# pin.net
KiCad netlist of a schematic drawn in EAGLE
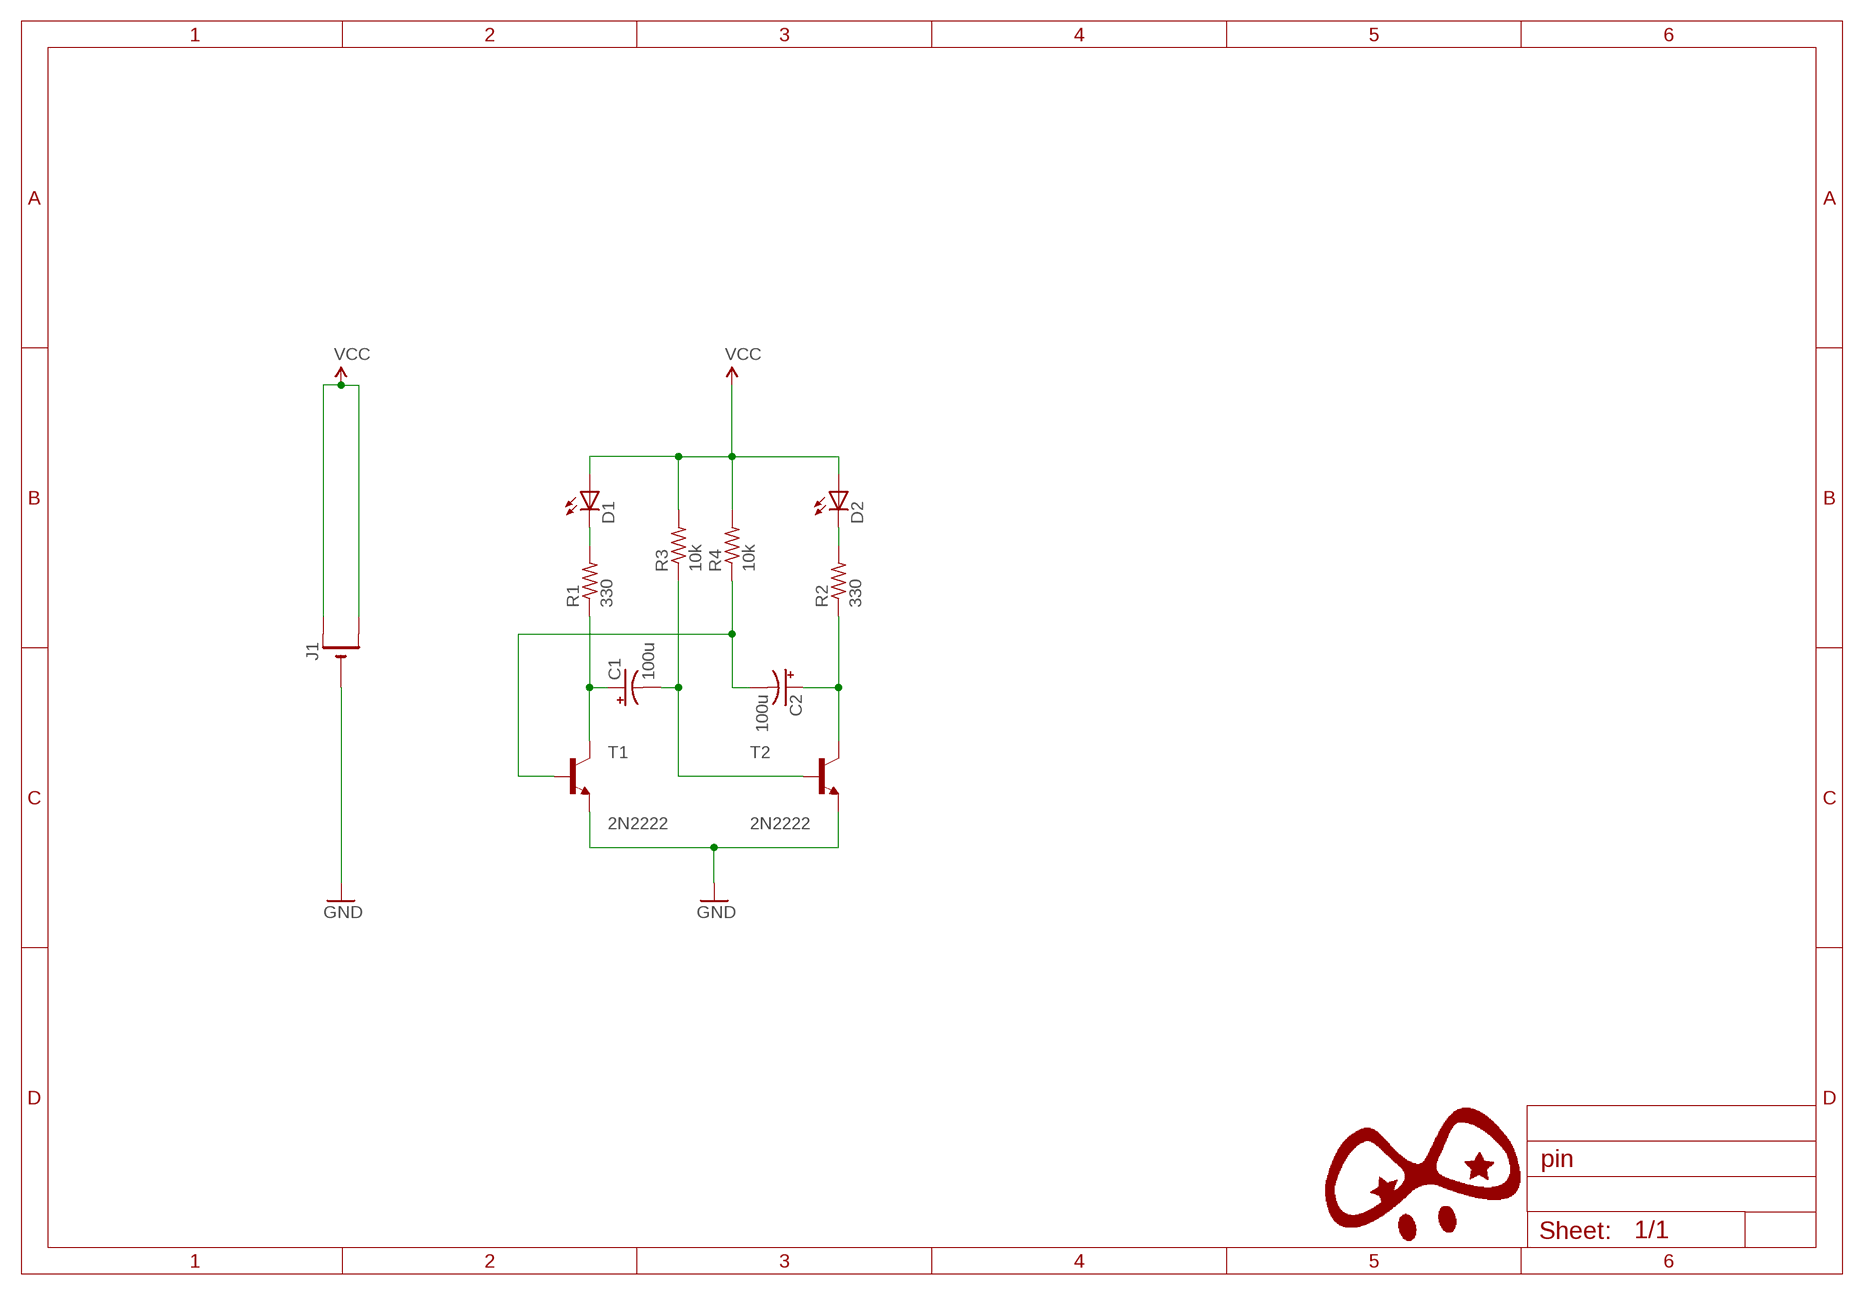
[diagram p0: schematic, sheet 1]

(export (version "E")
  (design (tool "Eeschema 10.0.6"))
  (components
    (comp (ref "C1")
      (value "100u")
      (footprint "eagle-import:E2-5")
      (libsource (lib "eagle-import") (part "CPOL-USE2-5"))
    )
    (comp (ref "C2")
      (value "100u")
      (footprint "eagle-import:E2-5")
      (libsource (lib "eagle-import") (part "CPOL-USE2-5"))
    )
    (comp (ref "D1")
      (value "LED-3MM")
      (footprint "eagle-import:LED_3MM")
      (libsource (lib "eagle-import") (part "LED-3MM"))
    )
    (comp (ref "D2")
      (value "LED-3MM")
      (footprint "eagle-import:LED_3MM")
      (libsource (lib "eagle-import") (part "LED-3MM"))
    )
    (comp (ref "J1")
      (value "CR1220SMT")
      (footprint "eagle-import:CR1220-SMD")
      (libsource (lib "eagle-import") (part "CR1220SMT"))
    )
    (comp (ref "R1")
      (value "330")
      (footprint "eagle-import:0204_5")
      (libsource (lib "eagle-import") (part "R-US_0204/5"))
    )
    (comp (ref "R2")
      (value "330")
      (footprint "eagle-import:0204_5")
      (libsource (lib "eagle-import") (part "R-US_0204/5"))
    )
    (comp (ref "R3")
      (value "10k")
      (footprint "eagle-import:0204_5")
      (libsource (lib "eagle-import") (part "R-US_0204/5"))
    )
    (comp (ref "R4")
      (value "10k")
      (footprint "eagle-import:0204_5")
      (libsource (lib "eagle-import") (part "R-US_0204/5"))
    )
    (comp (ref "T1")
      (value "2N2222")
      (footprint "eagle-import:TO92-EBC-OVAL")
      (libsource (lib "eagle-import") (part "2N2222"))
    )
    (comp (ref "T2")
      (value "2N2222")
      (footprint "eagle-import:TO92-EBC-OVAL")
      (libsource (lib "eagle-import") (part "2N2222"))
    )
  )
  (nets
    (net (code "1") (name "GND") (class "Default")
      (node (ref "J1") (pin "-") (pinfunction "-_-") (pintype "passive"))
      (node (ref "T1") (pin "E") (pinfunction "E_E") (pintype "passive"))
      (node (ref "T2") (pin "E") (pinfunction "E_E") (pintype "passive"))
    )
    (net (code "2") (name "Net-(C1-Pad+)") (class "Default")
      (node (ref "C1") (pin "+") (pinfunction "+_+") (pintype "passive"))
      (node (ref "R1") (pin "1") (pinfunction "1_1") (pintype "passive"))
      (node (ref "T1") (pin "C") (pinfunction "C_C") (pintype "passive"))
    )
    (net (code "3") (name "Net-(C1-Pad-)") (class "Default")
      (node (ref "C1") (pin "-") (pinfunction "-_-") (pintype "passive"))
      (node (ref "R3") (pin "1") (pinfunction "1_1") (pintype "passive"))
      (node (ref "T2") (pin "B") (pinfunction "B_B") (pintype "passive"))
    )
    (net (code "4") (name "Net-(C2-Pad+)") (class "Default")
      (node (ref "C2") (pin "+") (pinfunction "+_+") (pintype "passive"))
      (node (ref "R2") (pin "1") (pinfunction "1_1") (pintype "passive"))
      (node (ref "T2") (pin "C") (pinfunction "C_C") (pintype "passive"))
    )
    (net (code "5") (name "Net-(C2-Pad-)") (class "Default")
      (node (ref "C2") (pin "-") (pinfunction "-_-") (pintype "passive"))
      (node (ref "R4") (pin "1") (pinfunction "1_1") (pintype "passive"))
      (node (ref "T1") (pin "B") (pinfunction "B_B") (pintype "passive"))
    )
    (net (code "6") (name "Net-(D1-PadC)") (class "Default")
      (node (ref "D1") (pin "C") (pinfunction "C_C") (pintype "passive"))
      (node (ref "R1") (pin "2") (pinfunction "2_2") (pintype "passive"))
    )
    (net (code "7") (name "Net-(D2-PadC)") (class "Default")
      (node (ref "D2") (pin "C") (pinfunction "C_C") (pintype "passive"))
      (node (ref "R2") (pin "2") (pinfunction "2_2") (pintype "passive"))
    )
    (net (code "8") (name "VCC") (class "Default")
      (node (ref "D1") (pin "A") (pinfunction "A_A") (pintype "passive"))
      (node (ref "D2") (pin "A") (pinfunction "A_A") (pintype "passive"))
      (node (ref "J1") (pin "+$1") (pinfunction "+_+$1") (pintype "passive"))
      (node (ref "J1") (pin "+$2") (pinfunction "+1_+$2") (pintype "passive"))
      (node (ref "R3") (pin "2") (pinfunction "2_2") (pintype "passive"))
      (node (ref "R4") (pin "2") (pinfunction "2_2") (pintype "passive"))
    )
  )
)
